# EasyCAN_diy.net
KiCad netlist of a schematic drawn in EAGLE
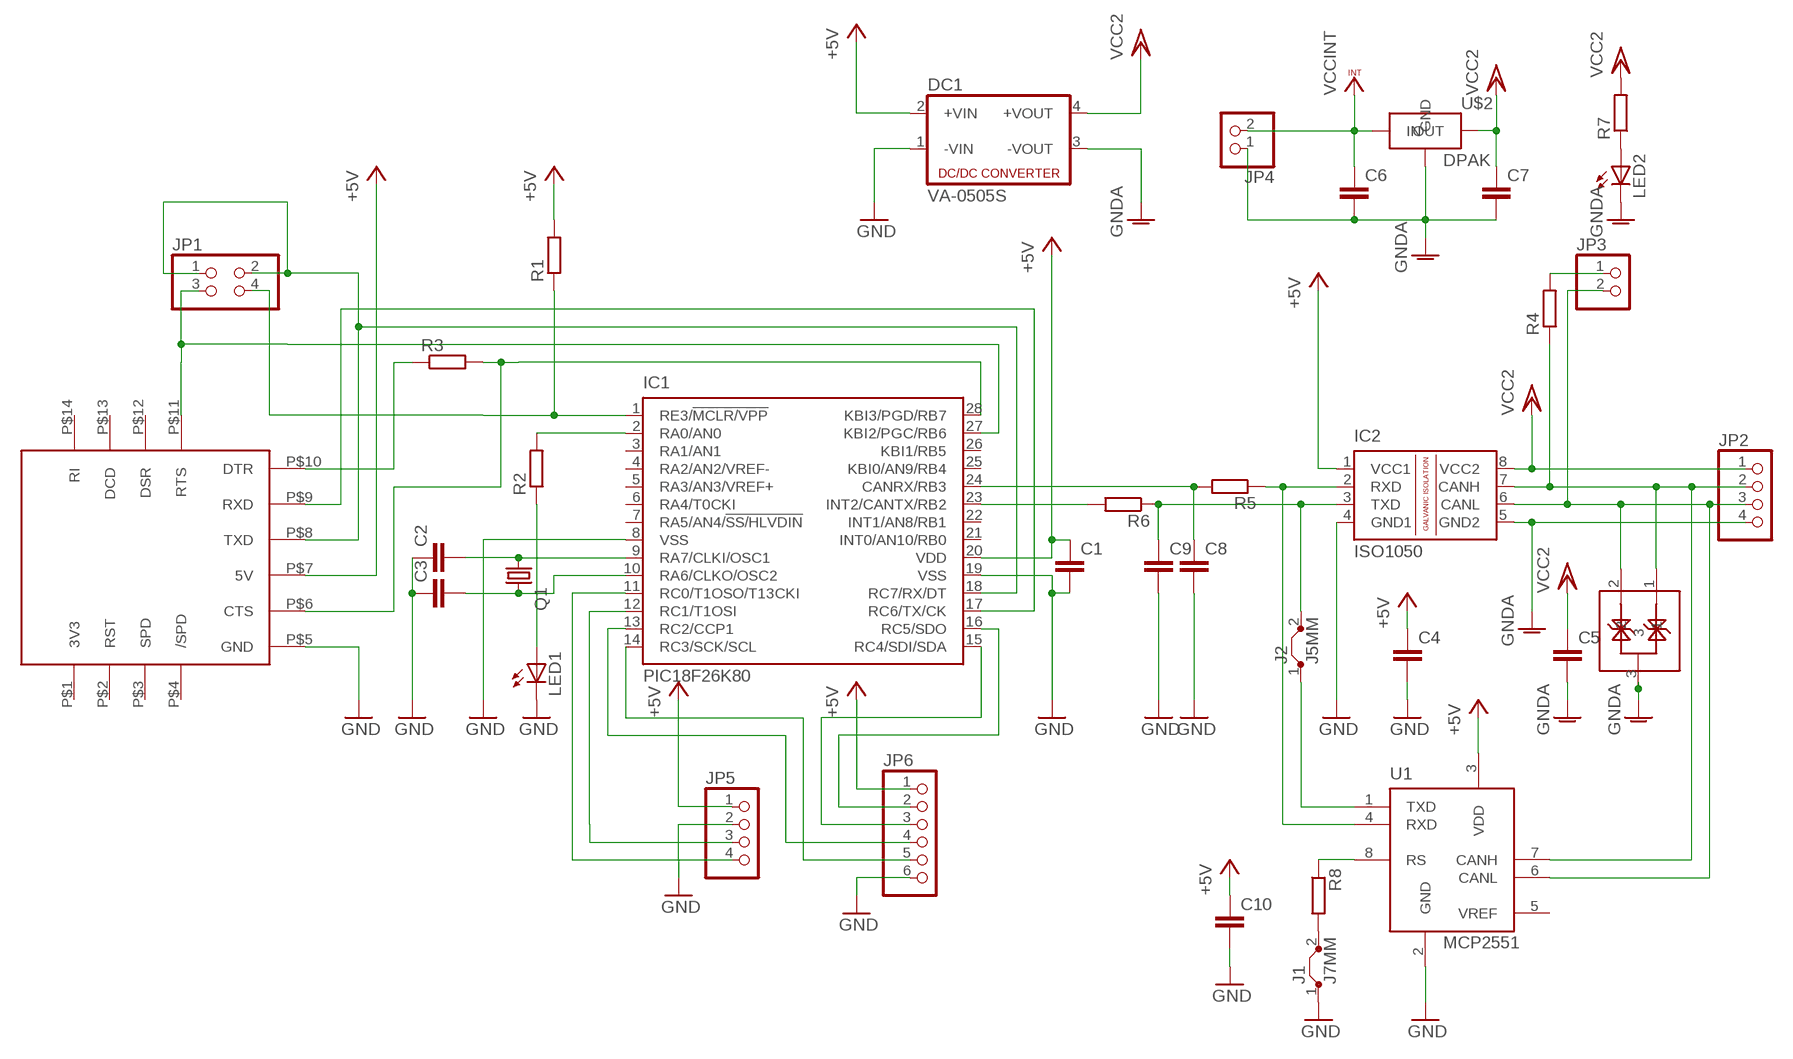
[diagram p0: schematic, sheet 1]

(export (version "E")
  (design (tool "Eeschema 10.0.6"))
  (components
    (comp (ref "C1")
      (value "C-EUC1206")
      (footprint "eagle-import:C1206")
      (libsource (lib "eagle-import") (part "C-EUC1206"))
    )
    (comp (ref "C2")
      (value "C-EUC1206")
      (footprint "eagle-import:C1206")
      (libsource (lib "eagle-import") (part "C-EUC1206"))
    )
    (comp (ref "C3")
      (value "C-EUC1206")
      (footprint "eagle-import:C1206")
      (libsource (lib "eagle-import") (part "C-EUC1206"))
    )
    (comp (ref "C4")
      (value "C-EUC1206")
      (footprint "eagle-import:C1206")
      (libsource (lib "eagle-import") (part "C-EUC1206"))
    )
    (comp (ref "C5")
      (value "C-EUC1206")
      (footprint "eagle-import:C1206")
      (libsource (lib "eagle-import") (part "C-EUC1206"))
    )
    (comp (ref "C6")
      (value "C-EUC1206")
      (footprint "eagle-import:C1206")
      (libsource (lib "eagle-import") (part "C-EUC1206"))
    )
    (comp (ref "C7")
      (value "C-EUC1206")
      (footprint "eagle-import:C1206")
      (libsource (lib "eagle-import") (part "C-EUC1206"))
    )
    (comp (ref "C8")
      (value "C-EUC1206")
      (footprint "eagle-import:C1206")
      (libsource (lib "eagle-import") (part "C-EUC1206"))
    )
    (comp (ref "C9")
      (value "C-EUC1206")
      (footprint "eagle-import:C1206")
      (libsource (lib "eagle-import") (part "C-EUC1206"))
    )
    (comp (ref "C10")
      (value "C-EUC1206")
      (footprint "eagle-import:C1206")
      (libsource (lib "eagle-import") (part "C-EUC1206"))
    )
    (comp (ref "D1")
      (value "NUP2105L")
      (footprint "eagle-import:TO236")
      (libsource (lib "eagle-import") (part "NUP2105L"))
    )
    (comp (ref "DC1")
      (value "VA-0505S")
      (footprint "eagle-import:4SIL")
      (libsource (lib "eagle-import") (part "VA-?S0505"))
    )
    (comp (ref "IC1")
      (value "PIC18F26K80")
      (footprint "eagle-import:SO28W")
      (libsource (lib "eagle-import") (part "PIC18F26K80-E/SO"))
    )
    (comp (ref "IC2")
      (value "ISO1050")
      (footprint "eagle-import:DUB-R-PDSO-G8")
      (fields (field (name "MPN") "ISO1050DUBR"))
      (libsource (lib "eagle-import") (part "ISO1050DUB"))
    )
    (comp (ref "J1")
      (value "J7MM")
      (footprint "eagle-import:07")
      (libsource (lib "eagle-import") (part "J7MM"))
    )
    (comp (ref "J2")
      (value "J5MM")
      (footprint "eagle-import:05")
      (libsource (lib "eagle-import") (part "J5MM"))
    )
    (comp (ref "JP1")
      (value "PINHD-2X2")
      (footprint "eagle-import:2X02")
      (libsource (lib "eagle-import") (part "PINHD-2X2"))
    )
    (comp (ref "JP2")
      (value "PINHD-1X4")
      (footprint "eagle-import:1X04")
      (libsource (lib "eagle-import") (part "PINHD-1X4"))
    )
    (comp (ref "JP3")
      (value "PINHD-1X2")
      (footprint "eagle-import:1X02")
      (libsource (lib "eagle-import") (part "PINHD-1X2"))
    )
    (comp (ref "JP4")
      (value "PINHD-1X2")
      (footprint "eagle-import:1X02")
      (libsource (lib "eagle-import") (part "PINHD-1X2"))
    )
    (comp (ref "JP5")
      (value "PINHD-1X4")
      (footprint "eagle-import:1X04")
      (libsource (lib "eagle-import") (part "PINHD-1X4"))
    )
    (comp (ref "JP6")
      (value "PINHD-1X6")
      (footprint "eagle-import:1X06")
      (libsource (lib "eagle-import") (part "PINHD-1X6"))
    )
    (comp (ref "LED1")
      (value "LEDSML1206")
      (footprint "eagle-import:SML1206")
      (libsource (lib "eagle-import") (part "LEDSML1206"))
    )
    (comp (ref "LED2")
      (value "LEDSML1206")
      (footprint "eagle-import:SML1206")
      (libsource (lib "eagle-import") (part "LEDSML1206"))
    )
    (comp (ref "Q1")
      (value "CRYSTALHC49UP")
      (footprint "eagle-import:HC49UP")
      (libsource (lib "eagle-import") (part "CRYSTALHC49UP"))
    )
    (comp (ref "R1")
      (value "R-EU_R1206")
      (footprint "eagle-import:R1206")
      (libsource (lib "eagle-import") (part "R-EU_R1206"))
    )
    (comp (ref "R2")
      (value "R-EU_R1206")
      (footprint "eagle-import:R1206")
      (libsource (lib "eagle-import") (part "R-EU_R1206"))
    )
    (comp (ref "R3")
      (value "R-EU_R1206")
      (footprint "eagle-import:R1206")
      (libsource (lib "eagle-import") (part "R-EU_R1206"))
    )
    (comp (ref "R4")
      (value "R-EU_0204/7")
      (footprint "eagle-import:0204_7")
      (libsource (lib "eagle-import") (part "R-EU_0204/7"))
    )
    (comp (ref "R5")
      (value "R-EU_R1206")
      (footprint "eagle-import:R1206")
      (libsource (lib "eagle-import") (part "R-EU_R1206"))
    )
    (comp (ref "R6")
      (value "R-EU_R1206")
      (footprint "eagle-import:R1206")
      (libsource (lib "eagle-import") (part "R-EU_R1206"))
    )
    (comp (ref "R7")
      (value "R-EU_R1206")
      (footprint "eagle-import:R1206")
      (libsource (lib "eagle-import") (part "R-EU_R1206"))
    )
    (comp (ref "R8")
      (value "R-EU_R1206")
      (footprint "eagle-import:R1206")
      (libsource (lib "eagle-import") (part "R-EU_R1206"))
    )
    (comp (ref "U$1")
      (value "BTE13-007")
      (footprint "eagle-import:BTE13-007")
      (libsource (lib "eagle-import") (part "BTE13-007"))
    )
    (comp (ref "U$2")
      (value "7805-DPAK")
      (footprint "eagle-import:7805-DPAK")
      (libsource (lib "eagle-import") (part "7805-DPAK"))
    )
    (comp (ref "U1")
      (value "MCP2551")
      (footprint "eagle-import:SO-08")
      (libsource (lib "eagle-import") (part "MCP2551SO"))
    )
  )
  (nets
    (net (code "1") (name "+5V") (class "Default")
      (node (ref "C1") (pin "1") (pinfunction "1_1") (pintype "passive"))
      (node (ref "C10") (pin "1") (pinfunction "1_1") (pintype "passive"))
      (node (ref "C4") (pin "1") (pinfunction "1_1") (pintype "passive"))
      (node (ref "DC1") (pin "2") (pinfunction "+VIN_2") (pintype "passive"))
      (node (ref "IC1") (pin "20") (pinfunction "VDD_20") (pintype "power_in"))
      (node (ref "IC2") (pin "1") (pinfunction "VCC1_1") (pintype "input"))
      (node (ref "JP5") (pin "1") (pinfunction "1_1") (pintype "passive"))
      (node (ref "JP6") (pin "1") (pinfunction "1_1") (pintype "passive"))
      (node (ref "R1") (pin "2") (pinfunction "2_2") (pintype "passive"))
      (node (ref "U$1") (pin "P$7") (pinfunction "5V_P$7") (pintype "power_in"))
      (node (ref "U1") (pin "3") (pinfunction "VDD_3") (pintype "power_in"))
    )
    (net (code "2") (name "/3V3") (class "Default")
      (node (ref "U$1") (pin "P$1") (pinfunction "3V3_P$1") (pintype "power_in"))
    )
    (net (code "3") (name "GND") (class "Default")
      (node (ref "C1") (pin "2") (pinfunction "2_2") (pintype "passive"))
      (node (ref "C10") (pin "2") (pinfunction "2_2") (pintype "passive"))
      (node (ref "C2") (pin "1") (pinfunction "1_1") (pintype "passive"))
      (node (ref "C3") (pin "1") (pinfunction "1_1") (pintype "passive"))
      (node (ref "C4") (pin "2") (pinfunction "2_2") (pintype "passive"))
      (node (ref "C8") (pin "2") (pinfunction "2_2") (pintype "passive"))
      (node (ref "C9") (pin "2") (pinfunction "2_2") (pintype "passive"))
      (node (ref "DC1") (pin "1") (pinfunction "-VIN_1") (pintype "passive"))
      (node (ref "IC1") (pin "19") (pinfunction "VSS_19") (pintype "power_in"))
      (node (ref "IC1") (pin "8") (pinfunction "VSS_8") (pintype "power_in"))
      (node (ref "IC2") (pin "4") (pinfunction "GND1_4") (pintype "input"))
      (node (ref "J1") (pin "1") (pinfunction "1_1") (pintype "passive"))
      (node (ref "JP5") (pin "2") (pinfunction "2_2") (pintype "passive"))
      (node (ref "JP6") (pin "6") (pinfunction "6_6") (pintype "passive"))
      (node (ref "LED1") (pin "C") (pinfunction "C_C") (pintype "passive"))
      (node (ref "U$1") (pin "P$5") (pinfunction "GND_P$5") (pintype "power_in"))
      (node (ref "U1") (pin "2") (pinfunction "GND_2") (pintype "power_in"))
    )
    (net (code "4") (name "GNDA") (class "Default")
      (node (ref "C5") (pin "2") (pinfunction "2_2") (pintype "passive"))
      (node (ref "C6") (pin "2") (pinfunction "2_2") (pintype "passive"))
      (node (ref "C7") (pin "2") (pinfunction "2_2") (pintype "passive"))
      (node (ref "D1") (pin "3") (pinfunction "3_3") (pintype "bidirectional"))
      (node (ref "DC1") (pin "3") (pinfunction "-VOUT_3") (pintype "passive"))
      (node (ref "IC2") (pin "5") (pinfunction "GND2_5") (pintype "input"))
      (node (ref "JP2") (pin "4") (pinfunction "4_4") (pintype "passive"))
      (node (ref "JP4") (pin "1") (pinfunction "1_1") (pintype "passive"))
      (node (ref "LED2") (pin "C") (pinfunction "C_C") (pintype "passive"))
      (node (ref "U$2") (pin "GND") (pinfunction "GND_GND") (pintype "bidirectional"))
    )
    (net (code "5") (name "Net-(IC1-CANRX{slash}RB3)") (class "Default")
      (node (ref "C8") (pin "1") (pinfunction "1_1") (pintype "passive"))
      (node (ref "IC1") (pin "24") (pinfunction "CANRX/RB3_24") (pintype "bidirectional"))
      (node (ref "R5") (pin "2") (pinfunction "2_2") (pintype "passive"))
    )
    (net (code "6") (name "Net-(IC1-INT2{slash}CANTX{slash}RB2)") (class "Default")
      (node (ref "IC1") (pin "23") (pinfunction "INT2/CANTX/RB2_23") (pintype "bidirectional"))
      (node (ref "R6") (pin "2") (pinfunction "2_2") (pintype "passive"))
    )
    (net (code "7") (name "Net-(IC1-KBI2{slash}PGC{slash}RB6)") (class "Default")
      (node (ref "IC1") (pin "27") (pinfunction "KBI2/PGC/RB6_27") (pintype "bidirectional"))
      (node (ref "JP1") (pin "3") (pinfunction "3_3") (pintype "passive"))
      (node (ref "U$1") (pin "P$11") (pinfunction "RTS_P$11") (pintype "output"))
    )
    (net (code "8") (name "Net-(IC1-KBI3{slash}PGD{slash}RB7)") (class "Default")
      (node (ref "IC1") (pin "28") (pinfunction "KBI3/PGD/RB7_28") (pintype "bidirectional"))
      (node (ref "R3") (pin "2") (pinfunction "2_2") (pintype "passive"))
      (node (ref "U$1") (pin "P$6") (pinfunction "CTS_P$6") (pintype "input"))
    )
    (net (code "9") (name "Net-(IC1-RA0{slash}AN0)") (class "Default")
      (node (ref "IC1") (pin "2") (pinfunction "RA0/AN0_2") (pintype "bidirectional"))
      (node (ref "R2") (pin "2") (pinfunction "2_2") (pintype "passive"))
    )
    (net (code "10") (name "Net-(IC1-RA6{slash}CLKO{slash}OSC2)") (class "Default")
      (node (ref "C3") (pin "2") (pinfunction "2_2") (pintype "passive"))
      (node (ref "IC1") (pin "10") (pinfunction "RA6/CLKO/OSC2_10") (pintype "output"))
      (node (ref "Q1") (pin "1") (pinfunction "1_1") (pintype "passive"))
    )
    (net (code "11") (name "Net-(IC1-RA7{slash}CLKI{slash}OSC1)") (class "Default")
      (node (ref "C2") (pin "2") (pinfunction "2_2") (pintype "passive"))
      (node (ref "IC1") (pin "9") (pinfunction "RA7/CLKI/OSC1_9") (pintype "input"))
      (node (ref "Q1") (pin "2") (pinfunction "2_2") (pintype "passive"))
    )
    (net (code "12") (name "Net-(IC1-RC0{slash}T1OSO{slash}T13CKI)") (class "Default")
      (node (ref "IC1") (pin "11") (pinfunction "RC0/T1OSO/T13CKI_11") (pintype "bidirectional"))
      (node (ref "JP5") (pin "4") (pinfunction "4_4") (pintype "passive"))
    )
    (net (code "13") (name "Net-(IC1-RC1{slash}T1OSI)") (class "Default")
      (node (ref "IC1") (pin "12") (pinfunction "RC1/T1OSI_12") (pintype "bidirectional"))
      (node (ref "JP5") (pin "3") (pinfunction "3_3") (pintype "passive"))
    )
    (net (code "14") (name "Net-(IC1-RC2{slash}CCP1)") (class "Default")
      (node (ref "IC1") (pin "13") (pinfunction "RC2/CCP1_13") (pintype "bidirectional"))
      (node (ref "JP6") (pin "4") (pinfunction "4_4") (pintype "passive"))
    )
    (net (code "15") (name "Net-(IC1-RC3{slash}SCK{slash}SCL)") (class "Default")
      (node (ref "IC1") (pin "14") (pinfunction "RC3/SCK/SCL_14") (pintype "bidirectional"))
      (node (ref "JP6") (pin "5") (pinfunction "5_5") (pintype "passive"))
    )
    (net (code "16") (name "Net-(IC1-RC4{slash}SDI{slash}SDA)") (class "Default")
      (node (ref "IC1") (pin "15") (pinfunction "RC4/SDI/SDA_15") (pintype "bidirectional"))
      (node (ref "JP6") (pin "3") (pinfunction "3_3") (pintype "passive"))
    )
    (net (code "17") (name "Net-(IC1-RC5{slash}SDO)") (class "Default")
      (node (ref "IC1") (pin "16") (pinfunction "RC5/SDO_16") (pintype "bidirectional"))
      (node (ref "JP6") (pin "2") (pinfunction "2_2") (pintype "passive"))
    )
    (net (code "18") (name "Net-(IC1-RC6{slash}TX{slash}CK)") (class "Default")
      (node (ref "IC1") (pin "17") (pinfunction "RC6/TX/CK_17") (pintype "bidirectional"))
      (node (ref "U$1") (pin "P$9") (pinfunction "RXD_P$9") (pintype "input"))
    )
    (net (code "19") (name "Net-(IC1-RC7{slash}RX{slash}DT)") (class "Default")
      (node (ref "IC1") (pin "18") (pinfunction "RC7/RX/DT_18") (pintype "bidirectional"))
      (node (ref "JP1") (pin "1") (pinfunction "1_1") (pintype "passive"))
      (node (ref "JP1") (pin "2") (pinfunction "2_2") (pintype "passive"))
      (node (ref "U$1") (pin "P$8") (pinfunction "TXD_P$8") (pintype "output"))
    )
    (net (code "20") (name "Net-(IC1-RE3{slash}~{MCLR{slash}VPP})") (class "Default")
      (node (ref "IC1") (pin "1") (pinfunction "RE3/~{MCLR/VPP}_1") (pintype "input"))
      (node (ref "JP1") (pin "4") (pinfunction "4_4") (pintype "passive"))
      (node (ref "R1") (pin "1") (pinfunction "1_1") (pintype "passive"))
    )
    (net (code "21") (name "Net-(IC2-CANH)") (class "Default")
      (node (ref "D1") (pin "1") (pinfunction "1_1") (pintype "bidirectional"))
      (node (ref "IC2") (pin "7") (pinfunction "CANH_7") (pintype "input"))
      (node (ref "JP2") (pin "2") (pinfunction "2_2") (pintype "passive"))
      (node (ref "R4") (pin "1") (pinfunction "1_1") (pintype "passive"))
      (node (ref "U1") (pin "7") (pinfunction "CANH_7") (pintype "bidirectional"))
    )
    (net (code "22") (name "Net-(IC2-CANL)") (class "Default")
      (node (ref "D1") (pin "2") (pinfunction "2_2") (pintype "bidirectional"))
      (node (ref "IC2") (pin "6") (pinfunction "CANL_6") (pintype "input"))
      (node (ref "JP2") (pin "3") (pinfunction "3_3") (pintype "passive"))
      (node (ref "JP3") (pin "2") (pinfunction "2_2") (pintype "passive"))
      (node (ref "U1") (pin "6") (pinfunction "CANL_6") (pintype "bidirectional"))
    )
    (net (code "23") (name "Net-(IC2-RXD)") (class "Default")
      (node (ref "IC2") (pin "2") (pinfunction "RXD_2") (pintype "input"))
      (node (ref "R5") (pin "1") (pinfunction "1_1") (pintype "passive"))
      (node (ref "U1") (pin "4") (pinfunction "RXD_4") (pintype "output"))
    )
    (net (code "24") (name "Net-(IC2-TXD)") (class "Default")
      (node (ref "C9") (pin "1") (pinfunction "1_1") (pintype "passive"))
      (node (ref "IC2") (pin "3") (pinfunction "TXD_3") (pintype "input"))
      (node (ref "J2") (pin "2") (pinfunction "2_2") (pintype "passive"))
      (node (ref "R6") (pin "1") (pinfunction "1_1") (pintype "passive"))
    )
    (net (code "25") (name "Net-(J1-Pad2)") (class "Default")
      (node (ref "J1") (pin "2") (pinfunction "2_2") (pintype "passive"))
      (node (ref "R8") (pin "2") (pinfunction "2_2") (pintype "passive"))
    )
    (net (code "26") (name "Net-(JP3-Pad1)") (class "Default")
      (node (ref "JP3") (pin "1") (pinfunction "1_1") (pintype "passive"))
      (node (ref "R4") (pin "2") (pinfunction "2_2") (pintype "passive"))
    )
    (net (code "27") (name "Net-(LED1-PadA)") (class "Default")
      (node (ref "LED1") (pin "A") (pinfunction "A_A") (pintype "passive"))
      (node (ref "R2") (pin "1") (pinfunction "1_1") (pintype "passive"))
    )
    (net (code "28") (name "Net-(LED2-PadA)") (class "Default")
      (node (ref "LED2") (pin "A") (pinfunction "A_A") (pintype "passive"))
      (node (ref "R7") (pin "1") (pinfunction "1_1") (pintype "passive"))
    )
    (net (code "29") (name "Net-(U$1-DTR)") (class "Default")
      (node (ref "R3") (pin "1") (pinfunction "1_1") (pintype "passive"))
      (node (ref "U$1") (pin "P$10") (pinfunction "DTR_P$10") (pintype "output"))
    )
    (net (code "30") (name "Net-(U1-RS)") (class "Default")
      (node (ref "R8") (pin "1") (pinfunction "1_1") (pintype "passive"))
      (node (ref "U1") (pin "8") (pinfunction "RS_8") (pintype "input"))
    )
    (net (code "31") (name "Net-(U1-TXD)") (class "Default")
      (node (ref "J2") (pin "1") (pinfunction "1_1") (pintype "passive"))
      (node (ref "U1") (pin "1") (pinfunction "TXD_1") (pintype "input"))
    )
    (net (code "32") (name "VCC2") (class "Default")
      (node (ref "C5") (pin "1") (pinfunction "1_1") (pintype "passive"))
      (node (ref "C7") (pin "1") (pinfunction "1_1") (pintype "passive"))
      (node (ref "DC1") (pin "4") (pinfunction "+VOUT_4") (pintype "passive"))
      (node (ref "IC2") (pin "8") (pinfunction "VCC2_8") (pintype "input"))
      (node (ref "JP2") (pin "1") (pinfunction "1_1") (pintype "passive"))
      (node (ref "R7") (pin "2") (pinfunction "2_2") (pintype "passive"))
      (node (ref "U$2") (pin "OUT") (pinfunction "OUT_OUT") (pintype "bidirectional"))
    )
    (net (code "33") (name "VCCINT") (class "Default")
      (node (ref "C6") (pin "1") (pinfunction "1_1") (pintype "passive"))
      (node (ref "JP4") (pin "2") (pinfunction "2_2") (pintype "passive"))
      (node (ref "U$2") (pin "IN") (pinfunction "IN_IN") (pintype "bidirectional"))
    )
    (net (code "34") (name "unconnected-(IC1-INT0{slash}AN10{slash}RB0-Pad21)") (class "Default")
      (node (ref "IC1") (pin "21") (pinfunction "INT0/AN10/RB0_21") (pintype "bidirectional"))
    )
    (net (code "35") (name "unconnected-(IC1-INT1{slash}AN8{slash}RB1-Pad22)") (class "Default")
      (node (ref "IC1") (pin "22") (pinfunction "INT1/AN8/RB1_22") (pintype "bidirectional"))
    )
    (net (code "36") (name "unconnected-(IC1-KBI0{slash}AN9{slash}RB4-Pad25)") (class "Default")
      (node (ref "IC1") (pin "25") (pinfunction "KBI0/AN9/RB4_25") (pintype "bidirectional"))
    )
    (net (code "37") (name "unconnected-(IC1-KBI1{slash}RB5-Pad26)") (class "Default")
      (node (ref "IC1") (pin "26") (pinfunction "KBI1/RB5_26") (pintype "bidirectional"))
    )
    (net (code "38") (name "unconnected-(IC1-RA1{slash}AN1-Pad3)") (class "Default")
      (node (ref "IC1") (pin "3") (pinfunction "RA1/AN1_3") (pintype "bidirectional"))
    )
    (net (code "39") (name "unconnected-(IC1-RA2{slash}AN2{slash}VREF--Pad4)") (class "Default")
      (node (ref "IC1") (pin "4") (pinfunction "RA2/AN2/VREF-_4") (pintype "bidirectional"))
    )
    (net (code "40") (name "unconnected-(IC1-RA3{slash}AN3{slash}VREF+-Pad5)") (class "Default")
      (node (ref "IC1") (pin "5") (pinfunction "RA3/AN3/VREF+_5") (pintype "bidirectional"))
    )
    (net (code "41") (name "unconnected-(IC1-RA4{slash}T0CKI-Pad6)") (class "Default")
      (node (ref "IC1") (pin "6") (pinfunction "RA4/T0CKI_6") (pintype "bidirectional"))
    )
    (net (code "42") (name "unconnected-(IC1-RA5{slash}AN4{slash}~{SS{slash}HLVDIN}-Pad7)") (class "Default")
      (node (ref "IC1") (pin "7") (pinfunction "RA5/AN4/~{SS/HLVDIN}_7") (pintype "bidirectional"))
    )
    (net (code "43") (name "unconnected-(U$1-DCD-PadP$13)") (class "Default")
      (node (ref "U$1") (pin "P$13") (pinfunction "DCD_P$13") (pintype "input"))
    )
    (net (code "44") (name "unconnected-(U$1-DSR-PadP$12)") (class "Default")
      (node (ref "U$1") (pin "P$12") (pinfunction "DSR_P$12") (pintype "input"))
    )
    (net (code "45") (name "unconnected-(U$1-RI-PadP$14)") (class "Default")
      (node (ref "U$1") (pin "P$14") (pinfunction "RI_P$14") (pintype "input"))
    )
    (net (code "46") (name "unconnected-(U$1-RST-PadP$2)") (class "Default")
      (node (ref "U$1") (pin "P$2") (pinfunction "RST_P$2") (pintype "input"))
    )
    (net (code "47") (name "unconnected-(U$1-SPD-PadP$3)") (class "Default")
      (node (ref "U$1") (pin "P$3") (pinfunction "SPD_P$3") (pintype "output"))
    )
    (net (code "48") (name "unconnected-(U$1-{slash}SPD-PadP$4)") (class "Default")
      (node (ref "U$1") (pin "P$4") (pinfunction "/SPD_P$4") (pintype "output"))
    )
    (net (code "49") (name "unconnected-(U1-VREF-Pad5)") (class "Default")
      (node (ref "U1") (pin "5") (pinfunction "VREF_5") (pintype "output"))
    )
  )
)
